# DAC-Bessel-LPF.net
KiCad netlist of a schematic drawn in Altium Designer
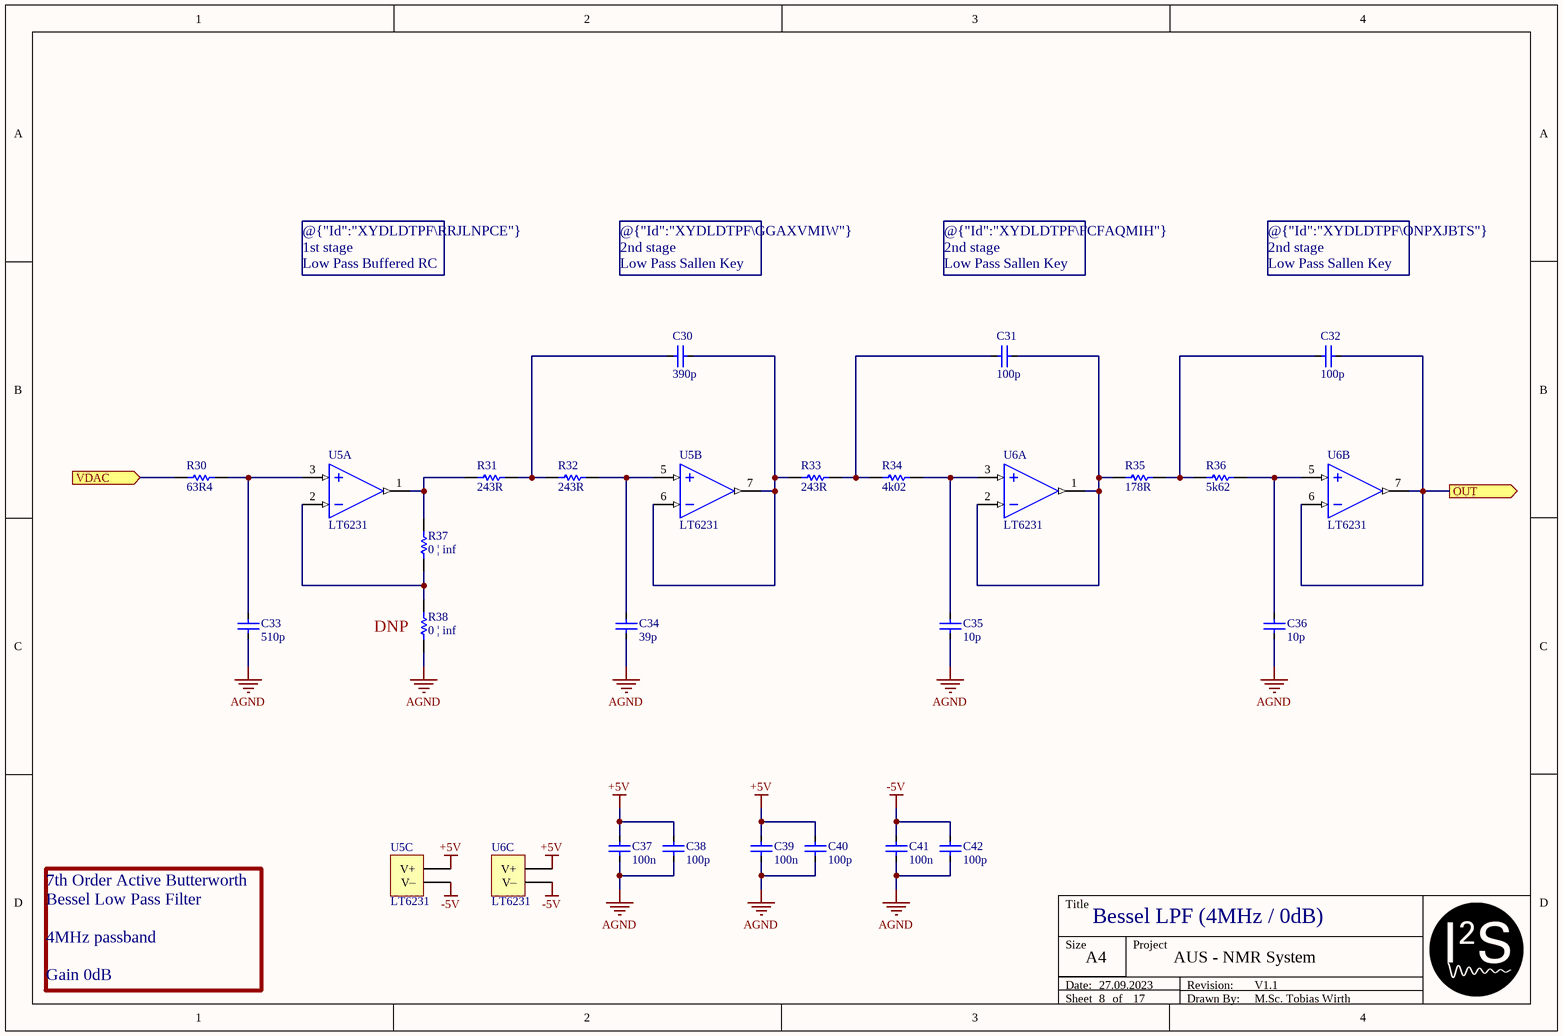
[diagram p0: DAC-Bessel-LPF.SchDoc]

(export (version "E")
  (design (tool "Eeschema 10.0.6"))
  (components
    (comp (ref "C30") (value "390p") (footprint "CAP_0402") (libsource (lib "IIS-Lib_TW") (part "Cap")))
    (comp (ref "C31") (value "100p") (footprint "CAP_0402") (libsource (lib "IIS-Lib_TW") (part "Cap")))
    (comp (ref "C32") (value "100p") (footprint "CAP_0402") (libsource (lib "IIS-Lib_TW") (part "Cap")))
    (comp (ref "C33") (value "510p") (footprint "CAP_0402") (libsource (lib "IIS-Lib_TW") (part "Cap")))
    (comp (ref "C34") (value "39p") (footprint "CAP_0402") (libsource (lib "IIS-Lib_TW") (part "Cap")))
    (comp (ref "C35") (value "10p") (footprint "CAP_0402") (libsource (lib "IIS-Lib_TW") (part "Cap")))
    (comp (ref "C36") (value "10p") (footprint "CAP_0402") (libsource (lib "IIS-Lib_TW") (part "Cap")))
    (comp (ref "C37") (value "100n") (footprint "CAP_0402") (libsource (lib "IIS-Lib_TW") (part "Cap")))
    (comp (ref "C38") (value "100p") (footprint "CAP_0402") (libsource (lib "IIS-Lib_TW") (part "Cap")))
    (comp (ref "C39") (value "100n") (footprint "CAP_0402") (libsource (lib "IIS-Lib_TW") (part "Cap")))
    (comp (ref "C40") (value "100p") (footprint "CAP_0402") (libsource (lib "IIS-Lib_TW") (part "Cap")))
    (comp (ref "C41") (value "100n") (footprint "CAP_0402") (libsource (lib "IIS-Lib_TW") (part "Cap")))
    (comp (ref "C42") (value "100p") (footprint "CAP_0402") (libsource (lib "IIS-Lib_TW") (part "Cap")))
    (comp (ref "R30") (value "63R4") (footprint "RES_0402") (libsource (lib "IIS-Lib_TW") (part "Res")))
    (comp (ref "R31") (value "243R") (footprint "RES_0402") (libsource (lib "IIS-Lib_TW") (part "Res")))
    (comp (ref "R32") (value "243R") (footprint "RES_0402") (libsource (lib "IIS-Lib_TW") (part "Res")))
    (comp (ref "R33") (value "243R") (footprint "RES_0402") (libsource (lib "IIS-Lib_TW") (part "Res")))
    (comp (ref "R34") (value "4k02") (footprint "RES_0402") (libsource (lib "IIS-Lib_TW") (part "Res")))
    (comp (ref "R35") (value "178R") (footprint "RES_0402") (libsource (lib "IIS-Lib_TW") (part "Res")))
    (comp (ref "R36") (value "5k62") (footprint "RES_0402") (libsource (lib "IIS-Lib_TW") (part "Res")))
    (comp (ref "R37") (value "0 ¦ inf") (footprint "RES_0402") (libsource (lib "IIS-Lib_TW") (part "Res")))
    (comp (ref "R38") (value "0 ¦ inf") (footprint "RES_0402") (libsource (lib "IIS-Lib_TW") (part "Res")))
    (comp (ref "U5")
      (value "LT6231")
      (footprint "SOP127P600X175-8N")
      (description "215MHz, Rail-to-Rail Output, 1.1nV/√Hz, 3.5mA Op Amp Family")
      (libsource (lib "IIS-Lib_TW") (part "LT6231"))
    )
    (comp (ref "U6")
      (value "LT6231")
      (footprint "SOP127P600X175-8N")
      (description "215MHz, Rail-to-Rail Output, 1.1nV/√Hz, 3.5mA Op Amp Family")
      (libsource (lib "") (part "LT6231_1"))
    )
  )
  (nets
    (net (code "1") (name "+5V") (class "Default")
      (node (ref "C37") (pin "1") (pinfunction "1_1") (pintype "passive"))
      (node (ref "C38") (pin "1") (pinfunction "1_1") (pintype "passive"))
      (node (ref "C39") (pin "1") (pinfunction "1_1") (pintype "passive"))
      (node (ref "C40") (pin "1") (pinfunction "1_1") (pintype "passive"))
      (node (ref "U5") (pin "8") (pinfunction "V+_8") (pintype "power_in"))
      (node (ref "U6") (pin "8") (pinfunction "V+_8") (pintype "power_in"))
    )
    (net (code "2") (name "-5V") (class "Default")
      (node (ref "C41") (pin "1") (pinfunction "1_1") (pintype "passive"))
      (node (ref "C42") (pin "1") (pinfunction "1_1") (pintype "passive"))
      (node (ref "U5") (pin "4") (pinfunction "V–_4") (pintype "power_in"))
      (node (ref "U6") (pin "4") (pinfunction "V–_4") (pintype "power_in"))
    )
    (net (code "3") (name "/OUT") (class "Default")
      (node (ref "C32") (pin "2") (pinfunction "2_2") (pintype "passive"))
      (node (ref "U6") (pin "6") (pinfunction "IN1-_6") (pintype "input"))
      (node (ref "U6") (pin "7") (pinfunction "OUT2_7") (pintype "output"))
    )
    (net (code "4") (name "/VDAC") (class "Default")
      (node (ref "R30") (pin "1") (pinfunction "1_1") (pintype "passive"))
    )
    (net (code "5") (name "AGND") (class "Default")
      (node (ref "C33") (pin "2") (pinfunction "2_2") (pintype "passive"))
      (node (ref "C34") (pin "2") (pinfunction "2_2") (pintype "passive"))
      (node (ref "C35") (pin "2") (pinfunction "2_2") (pintype "passive"))
      (node (ref "C36") (pin "2") (pinfunction "2_2") (pintype "passive"))
      (node (ref "C37") (pin "2") (pinfunction "2_2") (pintype "passive"))
      (node (ref "C38") (pin "2") (pinfunction "2_2") (pintype "passive"))
      (node (ref "C39") (pin "2") (pinfunction "2_2") (pintype "passive"))
      (node (ref "C40") (pin "2") (pinfunction "2_2") (pintype "passive"))
      (node (ref "C41") (pin "2") (pinfunction "2_2") (pintype "passive"))
      (node (ref "C42") (pin "2") (pinfunction "2_2") (pintype "passive"))
      (node (ref "R38") (pin "1") (pinfunction "1_1") (pintype "passive"))
    )
    (net (code "6") (name "Net-(C30-Pad1)") (class "Default")
      (node (ref "C30") (pin "1") (pinfunction "1_1") (pintype "passive"))
      (node (ref "R31") (pin "2") (pinfunction "2_2") (pintype "passive"))
      (node (ref "R32") (pin "1") (pinfunction "1_1") (pintype "passive"))
    )
    (net (code "7") (name "Net-(C31-Pad1)") (class "Default")
      (node (ref "C31") (pin "1") (pinfunction "1_1") (pintype "passive"))
      (node (ref "R33") (pin "2") (pinfunction "2_2") (pintype "passive"))
      (node (ref "R34") (pin "1") (pinfunction "1_1") (pintype "passive"))
    )
    (net (code "8") (name "Net-(C32-Pad1)") (class "Default")
      (node (ref "C32") (pin "1") (pinfunction "1_1") (pintype "passive"))
      (node (ref "R35") (pin "2") (pinfunction "2_2") (pintype "passive"))
      (node (ref "R36") (pin "1") (pinfunction "1_1") (pintype "passive"))
    )
    (net (code "9") (name "Net-(U5A-IN1+)") (class "Default")
      (node (ref "C33") (pin "1") (pinfunction "1_1") (pintype "passive"))
      (node (ref "R30") (pin "2") (pinfunction "2_2") (pintype "passive"))
      (node (ref "U5") (pin "3") (pinfunction "IN1+_3") (pintype "input"))
    )
    (net (code "10") (name "Net-(U5A-IN1-)") (class "Default")
      (node (ref "R37") (pin "1") (pinfunction "1_1") (pintype "passive"))
      (node (ref "R38") (pin "2") (pinfunction "2_2") (pintype "passive"))
      (node (ref "U5") (pin "2") (pinfunction "IN1-_2") (pintype "input"))
    )
    (net (code "11") (name "Net-(U5A-OUT1)") (class "Default")
      (node (ref "R31") (pin "1") (pinfunction "1_1") (pintype "passive"))
      (node (ref "R37") (pin "2") (pinfunction "2_2") (pintype "passive"))
      (node (ref "U5") (pin "1") (pinfunction "OUT1_1") (pintype "output"))
    )
    (net (code "12") (name "Net-(U5B-IN1+)") (class "Default")
      (node (ref "C34") (pin "1") (pinfunction "1_1") (pintype "passive"))
      (node (ref "R32") (pin "2") (pinfunction "2_2") (pintype "passive"))
      (node (ref "U5") (pin "5") (pinfunction "IN1+_5") (pintype "input"))
    )
    (net (code "13") (name "Net-(U5B-IN1-)") (class "Default")
      (node (ref "C30") (pin "2") (pinfunction "2_2") (pintype "passive"))
      (node (ref "R33") (pin "1") (pinfunction "1_1") (pintype "passive"))
      (node (ref "U5") (pin "6") (pinfunction "IN1-_6") (pintype "input"))
      (node (ref "U5") (pin "7") (pinfunction "OUT2_7") (pintype "output"))
    )
    (net (code "14") (name "Net-(U6A-IN1+)") (class "Default")
      (node (ref "C35") (pin "1") (pinfunction "1_1") (pintype "passive"))
      (node (ref "R34") (pin "2") (pinfunction "2_2") (pintype "passive"))
      (node (ref "U6") (pin "3") (pinfunction "IN1+_3") (pintype "input"))
    )
    (net (code "15") (name "Net-(U6A-IN1-)") (class "Default")
      (node (ref "C31") (pin "2") (pinfunction "2_2") (pintype "passive"))
      (node (ref "R35") (pin "1") (pinfunction "1_1") (pintype "passive"))
      (node (ref "U6") (pin "1") (pinfunction "OUT1_1") (pintype "output"))
      (node (ref "U6") (pin "2") (pinfunction "IN1-_2") (pintype "input"))
    )
    (net (code "16") (name "Net-(U6B-IN1+)") (class "Default")
      (node (ref "C36") (pin "1") (pinfunction "1_1") (pintype "passive"))
      (node (ref "R36") (pin "2") (pinfunction "2_2") (pintype "passive"))
      (node (ref "U6") (pin "5") (pinfunction "IN1+_5") (pintype "input"))
    )
  )
)
